# LV_Power_Supply.net
KiCad netlist of a schematic drawn in Altium Designer
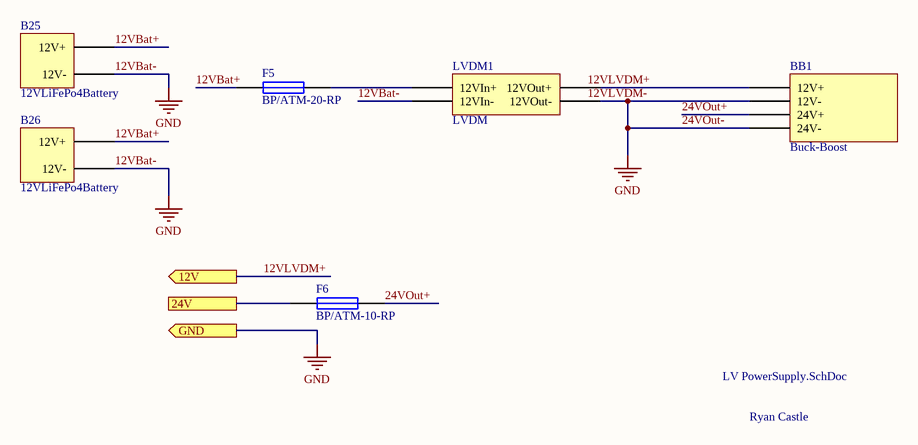
[diagram p0: LV Power Supply.SchDoc]

(export (version "E")
  (design (tool "Eeschema 10.0.6"))
  (components
    (comp (ref "B25") (value "12VLiFePo4Battery") (libsource (lib "Pod3") (part "12VLiFePo4Battery")))
    (comp (ref "B26") (value "12VLiFePo4Battery") (libsource (lib "Pod3") (part "12VLiFePo4Battery")))
    (comp (ref "BB1") (value "Buck-Boost") (libsource (lib "Pod3") (part "12-24 BuckBoost")))
    (comp (ref "F5")
      (value "BP/ATM-20-RP")
      (footprint "PIN-W2/E2.8")
      (description "Fuse")
      (fields (field (name "PUBLISHER") "Altium Limited"))
      (libsource (lib "Miscellaneous Devices") (part "Fuse 1"))
    )
    (comp (ref "F6")
      (value "BP/ATM-10-RP")
      (footprint "PIN-W2/E2.8")
      (description "Fuse")
      (fields (field (name "PUBLISHER") "Altium Limited"))
      (libsource (lib "Miscellaneous Devices") (part "Fuse 1"))
    )
    (comp (ref "LVDM1") (value "LVDM") (libsource (lib "Pod3") (part "LVDM")))
  )
  (nets
    (net (code "1") (name "/12VBat+") (class "Default")
      (node (ref "B25") (pin "1") (pinfunction "12V+_1") (pintype "passive"))
      (node (ref "B26") (pin "1") (pinfunction "12V+_1") (pintype "passive"))
      (node (ref "F5") (pin "1") (pinfunction "1_1") (pintype "passive"))
    )
    (net (code "4") (name "/24V") (class "Default")
      (node (ref "F6") (pin "1") (pinfunction "1_1") (pintype "passive"))
    )
    (net (code "5") (name "/24VOut+") (class "Default")
      (node (ref "BB1") (pin "14") (pinfunction "24V+_14") (pintype "passive"))
      (node (ref "F6") (pin "2") (pinfunction "2_2") (pintype "passive"))
    )
    (net (code "6") (name "GND") (class "Default")
      (node (ref "B25") (pin "2") (pinfunction "12V-_2") (pintype "passive"))
      (node (ref "B26") (pin "2") (pinfunction "12V-_2") (pintype "passive"))
      (node (ref "BB1") (pin "13") (pinfunction "24V-_13") (pintype "passive"))
      (node (ref "BB1") (pin "15") (pinfunction "12V-_15") (pintype "passive"))
      (node (ref "LVDM1") (pin "10") (pinfunction "12VIn-_10") (pintype "passive"))
      (node (ref "LVDM1") (pin "12") (pinfunction "12VOut-_12") (pintype "passive"))
    )
    (net (code "7") (name "Net-(BB1-12V+)") (class "Default")
      (node (ref "BB1") (pin "16") (pinfunction "12V+_16") (pintype "passive"))
      (node (ref "LVDM1") (pin "11") (pinfunction "12VOut+_11") (pintype "passive"))
    )
    (net (code "8") (name "Net-(LVDM1-12VIn+)") (class "Default")
      (node (ref "F5") (pin "2") (pinfunction "2_2") (pintype "passive"))
      (node (ref "LVDM1") (pin "9") (pinfunction "12VIn+_9") (pintype "passive"))
    )
  )
)
